# PCB-ARD-MMBOS.net
KiCad netlist of a schematic drawn in EAGLE
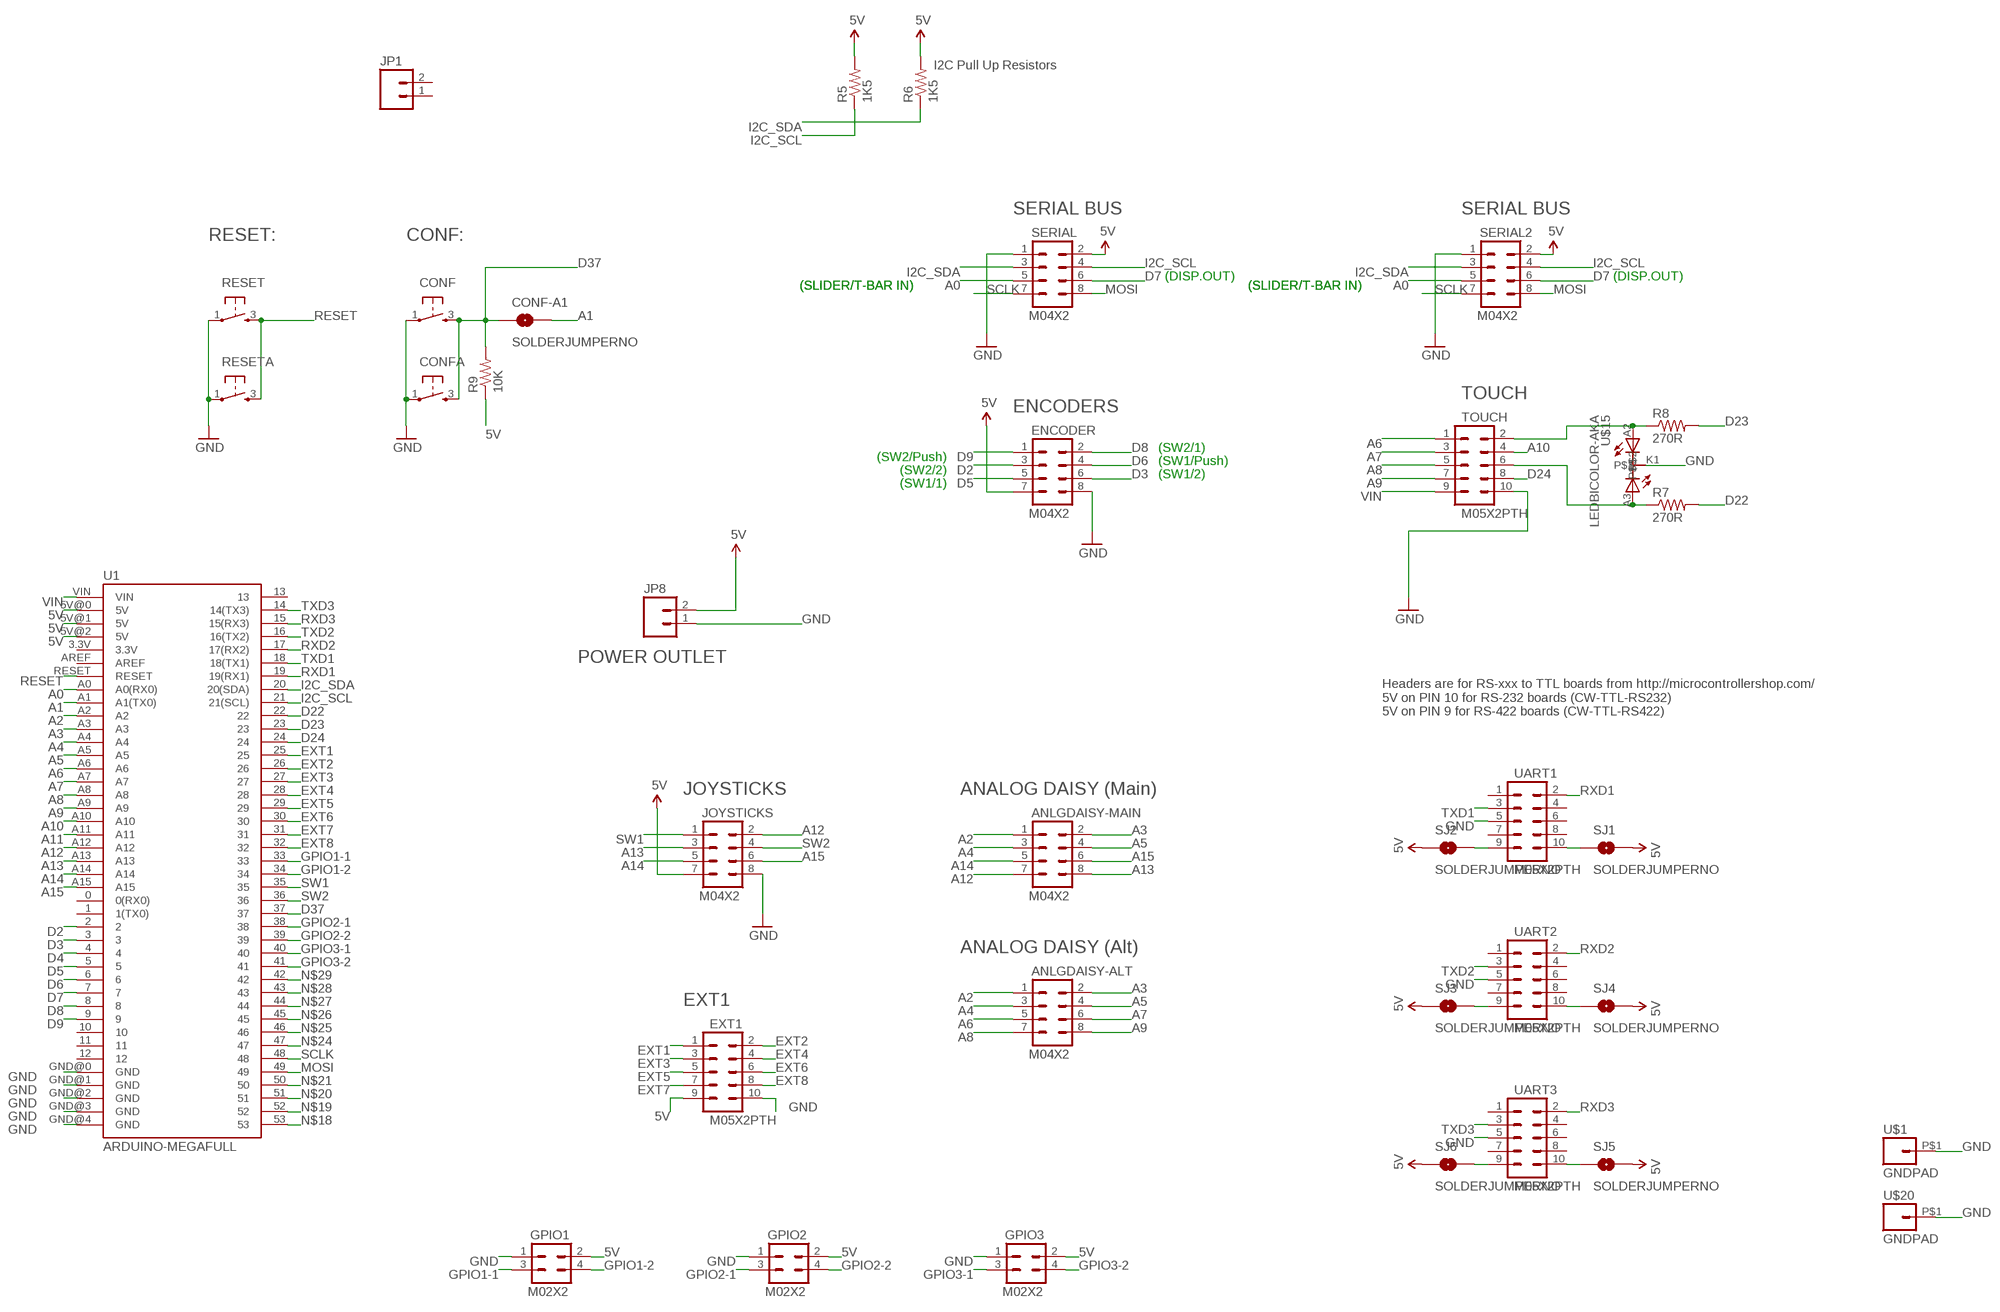
[diagram p0: schematic, sheet 1]

(export (version "E")
  (design (tool "Eeschema 10.0.6"))
  (components
    (comp (ref "ANLGDAISY-ALT")
      (value "M04X2")
      (footprint "eagle-import:2X4")
      (libsource (lib "eagle-import") (part "M04X2"))
    )
    (comp (ref "ANLGDAISY-MAIN")
      (value "M04X2")
      (footprint "eagle-import:2X4")
      (libsource (lib "eagle-import") (part "M04X2"))
    )
    (comp (ref "CONF")
      (value "TAC_SWITCH")
      (footprint "eagle-import:PUSHBUTTON")
      (libsource (lib "eagle-import") (part "TAC_SWITCH"))
    )
    (comp (ref "CONF-A1")
      (value "SOLDERJUMPERNO")
      (footprint "eagle-import:SJ_2S-NO")
      (libsource (lib "eagle-import") (part "SOLDERJUMPERNO"))
    )
    (comp (ref "CONFA")
      (value "TAC_SWITCH")
      (footprint "eagle-import:PUSHBUTTON")
      (libsource (lib "eagle-import") (part "TAC_SWITCH"))
    )
    (comp (ref "ENCODER")
      (value "M04X2")
      (footprint "eagle-import:2X4")
      (libsource (lib "eagle-import") (part "M04X2"))
    )
    (comp (ref "EXT1")
      (value "M05X2PTH")
      (footprint "eagle-import:AVR_ICSP")
      (libsource (lib "eagle-import") (part "M05X2PTH"))
    )
    (comp (ref "GPIO1")
      (value "M02X2")
      (footprint "eagle-import:2X2")
      (libsource (lib "eagle-import") (part "M02X2"))
    )
    (comp (ref "GPIO2")
      (value "M02X2")
      (footprint "eagle-import:2X2")
      (libsource (lib "eagle-import") (part "M02X2"))
    )
    (comp (ref "GPIO3")
      (value "M02X2")
      (footprint "eagle-import:2X2")
      (libsource (lib "eagle-import") (part "M02X2"))
    )
    (comp (ref "JOYSTICKS")
      (value "M04X2")
      (footprint "eagle-import:2X4")
      (libsource (lib "eagle-import") (part "M04X2"))
    )
    (comp (ref "JP1")
      (value "M02PTH")
      (footprint "eagle-import:1X02")
      (libsource (lib "eagle-import") (part "M02PTH"))
    )
    (comp (ref "JP8")
      (value "M02PTH4")
      (footprint "eagle-import:1X02_XTRA_BIG")
      (libsource (lib "eagle-import") (part "M02PTH4"))
    )
    (comp (ref "R5")
      (value "1K5")
      (footprint "eagle-import:0603-RES")
      (libsource (lib "eagle-import") (part "RESISTOR0603-RES"))
    )
    (comp (ref "R6")
      (value "1K5")
      (footprint "eagle-import:0603-RES")
      (libsource (lib "eagle-import") (part "RESISTOR0603-RES"))
    )
    (comp (ref "R7")
      (value "270R")
      (footprint "eagle-import:0603-RES")
      (libsource (lib "eagle-import") (part "RESISTOR0603-RES"))
    )
    (comp (ref "R8")
      (value "270R")
      (footprint "eagle-import:0603-RES")
      (libsource (lib "eagle-import") (part "RESISTOR0603-RES"))
    )
    (comp (ref "R9")
      (value "10K")
      (footprint "eagle-import:0603-RES")
      (libsource (lib "eagle-import") (part "RESISTOR0603-RES"))
    )
    (comp (ref "RESET")
      (value "TAC_SWITCH")
      (footprint "eagle-import:PUSHBUTTON")
      (libsource (lib "eagle-import") (part "TAC_SWITCH"))
    )
    (comp (ref "RESETA")
      (value "TAC_SWITCH")
      (footprint "eagle-import:PUSHBUTTON")
      (libsource (lib "eagle-import") (part "TAC_SWITCH"))
    )
    (comp (ref "SERIAL")
      (value "M04X2")
      (footprint "eagle-import:2X4")
      (libsource (lib "eagle-import") (part "M04X2"))
    )
    (comp (ref "SERIAL2")
      (value "M04X2")
      (footprint "eagle-import:2X4")
      (libsource (lib "eagle-import") (part "M04X2"))
    )
    (comp (ref "SJ1")
      (value "SOLDERJUMPERNO")
      (footprint "eagle-import:SJ_2S-NO")
      (libsource (lib "eagle-import") (part "SOLDERJUMPERNO"))
    )
    (comp (ref "SJ2")
      (value "SOLDERJUMPERNO")
      (footprint "eagle-import:SJ_2S-NO")
      (libsource (lib "eagle-import") (part "SOLDERJUMPERNO"))
    )
    (comp (ref "SJ3")
      (value "SOLDERJUMPERNO")
      (footprint "eagle-import:SJ_2S-NO")
      (libsource (lib "eagle-import") (part "SOLDERJUMPERNO"))
    )
    (comp (ref "SJ4")
      (value "SOLDERJUMPERNO")
      (footprint "eagle-import:SJ_2S-NO")
      (libsource (lib "eagle-import") (part "SOLDERJUMPERNO"))
    )
    (comp (ref "SJ5")
      (value "SOLDERJUMPERNO")
      (footprint "eagle-import:SJ_2S-NO")
      (libsource (lib "eagle-import") (part "SOLDERJUMPERNO"))
    )
    (comp (ref "SJ6")
      (value "SOLDERJUMPERNO")
      (footprint "eagle-import:SJ_2S-NO")
      (libsource (lib "eagle-import") (part "SOLDERJUMPERNO"))
    )
    (comp (ref "TOUCH")
      (value "M05X2PTH")
      (footprint "eagle-import:AVR_ICSP")
      (libsource (lib "eagle-import") (part "M05X2PTH"))
    )
    (comp (ref "U$1")
      (value "GNDPAD")
      (footprint "eagle-import:3.2MMPAD")
      (libsource (lib "eagle-import") (part "GNDPAD"))
    )
    (comp (ref "U$15")
      (value "LEDBICOLOR-AKA")
      (footprint "eagle-import:LED5MM-BICOLOR")
      (libsource (lib "eagle-import") (part "LEDBICOLOR-AKA"))
    )
    (comp (ref "U$20")
      (value "GNDPAD")
      (footprint "eagle-import:3.2MMPAD")
      (libsource (lib "eagle-import") (part "GNDPAD"))
    )
    (comp (ref "U1")
      (value "ARDUINO-MEGAFULL")
      (footprint "eagle-import:ARDUINO_MEGA")
      (libsource (lib "eagle-import") (part "ARDUINO-MEGAFULL"))
    )
    (comp (ref "UART1")
      (value "M05X2PTH")
      (footprint "eagle-import:AVR_ICSP")
      (libsource (lib "eagle-import") (part "M05X2PTH"))
    )
    (comp (ref "UART2")
      (value "M05X2PTH")
      (footprint "eagle-import:AVR_ICSP")
      (libsource (lib "eagle-import") (part "M05X2PTH"))
    )
    (comp (ref "UART3")
      (value "M05X2PTH")
      (footprint "eagle-import:AVR_ICSP")
      (libsource (lib "eagle-import") (part "M05X2PTH"))
    )
  )
  (nets
    (net (code "1") (name "/A0") (class "Default")
      (node (ref "SERIAL") (pin "5") (pinfunction "5_5") (pintype "passive"))
      (node (ref "SERIAL2") (pin "5") (pinfunction "5_5") (pintype "passive"))
      (node (ref "U1") (pin "A0") (pinfunction "A0(RX0)_A0") (pintype "bidirectional"))
    )
    (net (code "2") (name "/A1") (class "Default")
      (node (ref "CONF-A1") (pin "2") (pinfunction "2_2") (pintype "passive"))
      (node (ref "U1") (pin "A1") (pinfunction "A1(TX0)_A1") (pintype "bidirectional"))
    )
    (net (code "3") (name "/A2") (class "Default")
      (node (ref "ANLGDAISY-ALT") (pin "1") (pinfunction "1_1") (pintype "passive"))
      (node (ref "ANLGDAISY-MAIN") (pin "1") (pinfunction "1_1") (pintype "passive"))
      (node (ref "U1") (pin "A2") (pinfunction "A2_A2") (pintype "bidirectional"))
    )
    (net (code "4") (name "/A3") (class "Default")
      (node (ref "ANLGDAISY-ALT") (pin "2") (pinfunction "2_2") (pintype "passive"))
      (node (ref "ANLGDAISY-MAIN") (pin "2") (pinfunction "2_2") (pintype "passive"))
      (node (ref "U1") (pin "A3") (pinfunction "A3_A3") (pintype "bidirectional"))
    )
    (net (code "5") (name "/A4") (class "Default")
      (node (ref "ANLGDAISY-ALT") (pin "3") (pinfunction "3_3") (pintype "passive"))
      (node (ref "ANLGDAISY-MAIN") (pin "3") (pinfunction "3_3") (pintype "passive"))
      (node (ref "U1") (pin "A4") (pinfunction "A4_A4") (pintype "bidirectional"))
    )
    (net (code "6") (name "/A5") (class "Default")
      (node (ref "ANLGDAISY-ALT") (pin "4") (pinfunction "4_4") (pintype "passive"))
      (node (ref "ANLGDAISY-MAIN") (pin "4") (pinfunction "4_4") (pintype "passive"))
      (node (ref "U1") (pin "A5") (pinfunction "A5_A5") (pintype "bidirectional"))
    )
    (net (code "7") (name "/A6") (class "Default")
      (node (ref "ANLGDAISY-ALT") (pin "5") (pinfunction "5_5") (pintype "passive"))
      (node (ref "TOUCH") (pin "1") (pinfunction "1_1") (pintype "passive"))
      (node (ref "U1") (pin "A6") (pinfunction "A6_A6") (pintype "bidirectional"))
    )
    (net (code "8") (name "/A7") (class "Default")
      (node (ref "ANLGDAISY-ALT") (pin "6") (pinfunction "6_6") (pintype "passive"))
      (node (ref "TOUCH") (pin "3") (pinfunction "3_3") (pintype "passive"))
      (node (ref "U1") (pin "A7") (pinfunction "A7_A7") (pintype "bidirectional"))
    )
    (net (code "9") (name "/A8") (class "Default")
      (node (ref "ANLGDAISY-ALT") (pin "7") (pinfunction "7_7") (pintype "passive"))
      (node (ref "TOUCH") (pin "5") (pinfunction "5_5") (pintype "passive"))
      (node (ref "U1") (pin "A8") (pinfunction "A8_A8") (pintype "bidirectional"))
    )
    (net (code "10") (name "/A9") (class "Default")
      (node (ref "ANLGDAISY-ALT") (pin "8") (pinfunction "8_8") (pintype "passive"))
      (node (ref "TOUCH") (pin "7") (pinfunction "7_7") (pintype "passive"))
      (node (ref "U1") (pin "A9") (pinfunction "A9_A9") (pintype "bidirectional"))
    )
    (net (code "11") (name "/A10") (class "Default")
      (node (ref "TOUCH") (pin "4") (pinfunction "4_4") (pintype "passive"))
      (node (ref "U1") (pin "A10") (pinfunction "A10_A10") (pintype "bidirectional"))
    )
    (net (code "12") (name "/A11") (class "Default")
      (node (ref "U1") (pin "A11") (pinfunction "A11_A11") (pintype "bidirectional"))
    )
    (net (code "13") (name "/A12") (class "Default")
      (node (ref "ANLGDAISY-MAIN") (pin "7") (pinfunction "7_7") (pintype "passive"))
      (node (ref "JOYSTICKS") (pin "2") (pinfunction "2_2") (pintype "passive"))
      (node (ref "U1") (pin "A12") (pinfunction "A12_A12") (pintype "bidirectional"))
    )
    (net (code "14") (name "/A13") (class "Default")
      (node (ref "ANLGDAISY-MAIN") (pin "8") (pinfunction "8_8") (pintype "passive"))
      (node (ref "JOYSTICKS") (pin "3") (pinfunction "3_3") (pintype "passive"))
      (node (ref "U1") (pin "A13") (pinfunction "A13_A13") (pintype "bidirectional"))
    )
    (net (code "15") (name "/A14") (class "Default")
      (node (ref "ANLGDAISY-MAIN") (pin "5") (pinfunction "5_5") (pintype "passive"))
      (node (ref "JOYSTICKS") (pin "5") (pinfunction "5_5") (pintype "passive"))
      (node (ref "U1") (pin "A14") (pinfunction "A14_A14") (pintype "bidirectional"))
    )
    (net (code "16") (name "/A15") (class "Default")
      (node (ref "ANLGDAISY-MAIN") (pin "6") (pinfunction "6_6") (pintype "passive"))
      (node (ref "JOYSTICKS") (pin "6") (pinfunction "6_6") (pintype "passive"))
      (node (ref "U1") (pin "A15") (pinfunction "A15_A15") (pintype "bidirectional"))
    )
    (net (code "17") (name "/D2") (class "Default")
      (node (ref "ENCODER") (pin "3") (pinfunction "3_3") (pintype "passive"))
      (node (ref "U1") (pin "2") (pinfunction "2_2") (pintype "bidirectional"))
    )
    (net (code "18") (name "/D3") (class "Default")
      (node (ref "ENCODER") (pin "6") (pinfunction "6_6") (pintype "passive"))
      (node (ref "U1") (pin "3") (pinfunction "3_3") (pintype "bidirectional"))
    )
    (net (code "19") (name "/D4") (class "Default")
      (node (ref "U1") (pin "4") (pinfunction "4_4") (pintype "bidirectional"))
    )
    (net (code "20") (name "/D5") (class "Default")
      (node (ref "ENCODER") (pin "5") (pinfunction "5_5") (pintype "passive"))
      (node (ref "U1") (pin "5") (pinfunction "5_5") (pintype "bidirectional"))
    )
    (net (code "21") (name "/D6") (class "Default")
      (node (ref "ENCODER") (pin "4") (pinfunction "4_4") (pintype "passive"))
      (node (ref "U1") (pin "6") (pinfunction "6_6") (pintype "bidirectional"))
    )
    (net (code "22") (name "/D7") (class "Default")
      (node (ref "SERIAL") (pin "6") (pinfunction "6_6") (pintype "passive"))
      (node (ref "SERIAL2") (pin "6") (pinfunction "6_6") (pintype "passive"))
      (node (ref "U1") (pin "7") (pinfunction "7_7") (pintype "bidirectional"))
    )
    (net (code "23") (name "/D8") (class "Default")
      (node (ref "ENCODER") (pin "2") (pinfunction "2_2") (pintype "passive"))
      (node (ref "U1") (pin "8") (pinfunction "8_8") (pintype "bidirectional"))
    )
    (net (code "24") (name "/D9") (class "Default")
      (node (ref "ENCODER") (pin "1") (pinfunction "1_1") (pintype "passive"))
      (node (ref "U1") (pin "9") (pinfunction "9_9") (pintype "bidirectional"))
    )
    (net (code "25") (name "/D22") (class "Default")
      (node (ref "R7") (pin "2") (pinfunction "2_2") (pintype "passive"))
      (node (ref "U1") (pin "22") (pinfunction "22_22") (pintype "bidirectional"))
    )
    (net (code "26") (name "/D23") (class "Default")
      (node (ref "R8") (pin "2") (pinfunction "2_2") (pintype "passive"))
      (node (ref "U1") (pin "23") (pinfunction "23_23") (pintype "bidirectional"))
    )
    (net (code "27") (name "/D24") (class "Default")
      (node (ref "TOUCH") (pin "8") (pinfunction "8_8") (pintype "passive"))
      (node (ref "U1") (pin "24") (pinfunction "24_24") (pintype "bidirectional"))
    )
    (net (code "28") (name "/D37") (class "Default")
      (node (ref "CONF") (pin "3") (pinfunction "3_3") (pintype "passive"))
      (node (ref "CONF-A1") (pin "1") (pinfunction "1_1") (pintype "passive"))
      (node (ref "CONFA") (pin "3") (pinfunction "3_3") (pintype "passive"))
      (node (ref "R9") (pin "2") (pinfunction "2_2") (pintype "passive"))
      (node (ref "U1") (pin "37") (pinfunction "37_37") (pintype "bidirectional"))
    )
    (net (code "29") (name "/EXT1") (class "Default")
      (node (ref "EXT1") (pin "1") (pinfunction "1_1") (pintype "passive"))
      (node (ref "U1") (pin "25") (pinfunction "25_25") (pintype "bidirectional"))
    )
    (net (code "30") (name "/EXT2") (class "Default")
      (node (ref "EXT1") (pin "2") (pinfunction "2_2") (pintype "passive"))
      (node (ref "U1") (pin "26") (pinfunction "26_26") (pintype "bidirectional"))
    )
    (net (code "31") (name "/EXT3") (class "Default")
      (node (ref "EXT1") (pin "3") (pinfunction "3_3") (pintype "passive"))
      (node (ref "U1") (pin "27") (pinfunction "27_27") (pintype "bidirectional"))
    )
    (net (code "32") (name "/EXT4") (class "Default")
      (node (ref "EXT1") (pin "4") (pinfunction "4_4") (pintype "passive"))
      (node (ref "U1") (pin "28") (pinfunction "28_28") (pintype "bidirectional"))
    )
    (net (code "33") (name "/EXT5") (class "Default")
      (node (ref "EXT1") (pin "5") (pinfunction "5_5") (pintype "passive"))
      (node (ref "U1") (pin "29") (pinfunction "29_29") (pintype "bidirectional"))
    )
    (net (code "34") (name "/EXT6") (class "Default")
      (node (ref "EXT1") (pin "6") (pinfunction "6_6") (pintype "passive"))
      (node (ref "U1") (pin "30") (pinfunction "30_30") (pintype "bidirectional"))
    )
    (net (code "35") (name "/EXT7") (class "Default")
      (node (ref "EXT1") (pin "7") (pinfunction "7_7") (pintype "passive"))
      (node (ref "U1") (pin "31") (pinfunction "31_31") (pintype "bidirectional"))
    )
    (net (code "36") (name "/EXT8") (class "Default")
      (node (ref "EXT1") (pin "8") (pinfunction "8_8") (pintype "passive"))
      (node (ref "U1") (pin "32") (pinfunction "32_32") (pintype "bidirectional"))
    )
    (net (code "37") (name "/GPIO1-1") (class "Default")
      (node (ref "GPIO1") (pin "3") (pinfunction "3_3") (pintype "passive"))
      (node (ref "U1") (pin "33") (pinfunction "33_33") (pintype "bidirectional"))
    )
    (net (code "38") (name "/GPIO1-2") (class "Default")
      (node (ref "GPIO1") (pin "4") (pinfunction "4_4") (pintype "passive"))
      (node (ref "U1") (pin "34") (pinfunction "34_34") (pintype "bidirectional"))
    )
    (net (code "39") (name "/GPIO2-1") (class "Default")
      (node (ref "GPIO2") (pin "3") (pinfunction "3_3") (pintype "passive"))
      (node (ref "U1") (pin "38") (pinfunction "38_38") (pintype "bidirectional"))
    )
    (net (code "40") (name "/GPIO2-2") (class "Default")
      (node (ref "GPIO2") (pin "4") (pinfunction "4_4") (pintype "passive"))
      (node (ref "U1") (pin "39") (pinfunction "39_39") (pintype "bidirectional"))
    )
    (net (code "41") (name "/GPIO3-1") (class "Default")
      (node (ref "GPIO3") (pin "3") (pinfunction "3_3") (pintype "passive"))
      (node (ref "U1") (pin "40") (pinfunction "40_40") (pintype "bidirectional"))
    )
    (net (code "42") (name "/GPIO3-2") (class "Default")
      (node (ref "GPIO3") (pin "4") (pinfunction "4_4") (pintype "passive"))
      (node (ref "U1") (pin "41") (pinfunction "41_41") (pintype "bidirectional"))
    )
    (net (code "43") (name "/I2C_SCL") (class "Default")
      (node (ref "R5") (pin "1") (pinfunction "1_1") (pintype "passive"))
      (node (ref "SERIAL") (pin "4") (pinfunction "4_4") (pintype "passive"))
      (node (ref "SERIAL2") (pin "4") (pinfunction "4_4") (pintype "passive"))
      (node (ref "U1") (pin "21") (pinfunction "21(SCL)_21") (pintype "bidirectional"))
    )
    (net (code "44") (name "/I2C_SDA") (class "Default")
      (node (ref "R6") (pin "1") (pinfunction "1_1") (pintype "passive"))
      (node (ref "SERIAL") (pin "3") (pinfunction "3_3") (pintype "passive"))
      (node (ref "SERIAL2") (pin "3") (pinfunction "3_3") (pintype "passive"))
      (node (ref "U1") (pin "20") (pinfunction "20(SDA)_20") (pintype "bidirectional"))
    )
    (net (code "45") (name "/MOSI") (class "Default")
      (node (ref "SERIAL") (pin "8") (pinfunction "8_8") (pintype "passive"))
      (node (ref "SERIAL2") (pin "8") (pinfunction "8_8") (pintype "passive"))
      (node (ref "U1") (pin "49") (pinfunction "49_49") (pintype "bidirectional"))
    )
    (net (code "46") (name "/N$18") (class "Default")
      (node (ref "U1") (pin "53") (pinfunction "53_53") (pintype "bidirectional"))
    )
    (net (code "47") (name "/N$19") (class "Default")
      (node (ref "U1") (pin "52") (pinfunction "52_52") (pintype "bidirectional"))
    )
    (net (code "48") (name "/N$20") (class "Default")
      (node (ref "U1") (pin "51") (pinfunction "51_51") (pintype "bidirectional"))
    )
    (net (code "49") (name "/N$21") (class "Default")
      (node (ref "U1") (pin "50") (pinfunction "50_50") (pintype "bidirectional"))
    )
    (net (code "50") (name "/N$24") (class "Default")
      (node (ref "U1") (pin "47") (pinfunction "47_47") (pintype "bidirectional"))
    )
    (net (code "51") (name "/N$25") (class "Default")
      (node (ref "U1") (pin "46") (pinfunction "46_46") (pintype "bidirectional"))
    )
    (net (code "52") (name "/N$26") (class "Default")
      (node (ref "U1") (pin "45") (pinfunction "45_45") (pintype "bidirectional"))
    )
    (net (code "53") (name "/N$27") (class "Default")
      (node (ref "U1") (pin "44") (pinfunction "44_44") (pintype "bidirectional"))
    )
    (net (code "54") (name "/N$28") (class "Default")
      (node (ref "U1") (pin "43") (pinfunction "43_43") (pintype "bidirectional"))
    )
    (net (code "55") (name "/N$29") (class "Default")
      (node (ref "U1") (pin "42") (pinfunction "42_42") (pintype "bidirectional"))
    )
    (net (code "56") (name "/RESET") (class "Default")
      (node (ref "RESET") (pin "3") (pinfunction "3_3") (pintype "passive"))
      (node (ref "RESETA") (pin "3") (pinfunction "3_3") (pintype "passive"))
      (node (ref "U1") (pin "RESET") (pinfunction "RESET_RESET") (pintype "bidirectional"))
    )
    (net (code "57") (name "/RXD1") (class "Default")
      (node (ref "U1") (pin "19") (pinfunction "19(RX1)_19") (pintype "bidirectional"))
      (node (ref "UART1") (pin "2") (pinfunction "2_2") (pintype "passive"))
    )
    (net (code "58") (name "/RXD2") (class "Default")
      (node (ref "U1") (pin "17") (pinfunction "17(RX2)_17") (pintype "bidirectional"))
      (node (ref "UART2") (pin "2") (pinfunction "2_2") (pintype "passive"))
    )
    (net (code "59") (name "/RXD3") (class "Default")
      (node (ref "U1") (pin "15") (pinfunction "15(RX3)_15") (pintype "bidirectional"))
      (node (ref "UART3") (pin "2") (pinfunction "2_2") (pintype "passive"))
    )
    (net (code "60") (name "/SCLK") (class "Default")
      (node (ref "SERIAL") (pin "7") (pinfunction "7_7") (pintype "passive"))
      (node (ref "SERIAL2") (pin "7") (pinfunction "7_7") (pintype "passive"))
      (node (ref "U1") (pin "48") (pinfunction "48_48") (pintype "bidirectional"))
    )
    (net (code "61") (name "/SW1") (class "Default")
      (node (ref "JOYSTICKS") (pin "1") (pinfunction "1_1") (pintype "passive"))
      (node (ref "U1") (pin "35") (pinfunction "35_35") (pintype "bidirectional"))
    )
    (net (code "62") (name "/SW2") (class "Default")
      (node (ref "JOYSTICKS") (pin "4") (pinfunction "4_4") (pintype "passive"))
      (node (ref "U1") (pin "36") (pinfunction "36_36") (pintype "bidirectional"))
    )
    (net (code "63") (name "/TXD1") (class "Default")
      (node (ref "U1") (pin "18") (pinfunction "18(TX1)_18") (pintype "bidirectional"))
      (node (ref "UART1") (pin "3") (pinfunction "3_3") (pintype "passive"))
    )
    (net (code "64") (name "/TXD2") (class "Default")
      (node (ref "U1") (pin "16") (pinfunction "16(TX2)_16") (pintype "bidirectional"))
      (node (ref "UART2") (pin "3") (pinfunction "3_3") (pintype "passive"))
    )
    (net (code "65") (name "/TXD3") (class "Default")
      (node (ref "U1") (pin "14") (pinfunction "14(TX3)_14") (pintype "bidirectional"))
      (node (ref "UART3") (pin "3") (pinfunction "3_3") (pintype "passive"))
    )
    (net (code "66") (name "/VIN") (class "Default")
      (node (ref "TOUCH") (pin "9") (pinfunction "9_9") (pintype "passive"))
      (node (ref "U1") (pin "VIN") (pinfunction "VIN_VIN") (pintype "bidirectional"))
    )
    (net (code "67") (name "5V") (class "Default")
      (node (ref "ENCODER") (pin "7") (pinfunction "7_7") (pintype "passive"))
      (node (ref "EXT1") (pin "9") (pinfunction "9_9") (pintype "passive"))
      (node (ref "GPIO1") (pin "2") (pinfunction "2_2") (pintype "passive"))
      (node (ref "GPIO2") (pin "2") (pinfunction "2_2") (pintype "passive"))
      (node (ref "GPIO3") (pin "2") (pinfunction "2_2") (pintype "passive"))
      (node (ref "JOYSTICKS") (pin "7") (pinfunction "7_7") (pintype "passive"))
      (node (ref "JP8") (pin "2") (pinfunction "2_2") (pintype "passive"))
      (node (ref "R5") (pin "2") (pinfunction "2_2") (pintype "passive"))
      (node (ref "R6") (pin "2") (pinfunction "2_2") (pintype "passive"))
      (node (ref "R9") (pin "1") (pinfunction "1_1") (pintype "passive"))
      (node (ref "SERIAL") (pin "2") (pinfunction "2_2") (pintype "passive"))
      (node (ref "SERIAL2") (pin "2") (pinfunction "2_2") (pintype "passive"))
      (node (ref "SJ1") (pin "2") (pinfunction "2_2") (pintype "passive"))
      (node (ref "SJ2") (pin "1") (pinfunction "1_1") (pintype "passive"))
      (node (ref "SJ3") (pin "1") (pinfunction "1_1") (pintype "passive"))
      (node (ref "SJ4") (pin "2") (pinfunction "2_2") (pintype "passive"))
      (node (ref "SJ5") (pin "2") (pinfunction "2_2") (pintype "passive"))
      (node (ref "SJ6") (pin "1") (pinfunction "1_1") (pintype "passive"))
      (node (ref "U1") (pin "5V@0") (pinfunction "5V_5V@0") (pintype "bidirectional"))
      (node (ref "U1") (pin "5V@1") (pinfunction "5V_5V@1") (pintype "bidirectional"))
      (node (ref "U1") (pin "5V@2") (pinfunction "5V_5V@2") (pintype "bidirectional"))
    )
    (net (code "68") (name "GND") (class "Default")
      (node (ref "CONF") (pin "1") (pinfunction "1_1") (pintype "passive"))
      (node (ref "CONFA") (pin "1") (pinfunction "1_1") (pintype "passive"))
      (node (ref "ENCODER") (pin "8") (pinfunction "8_8") (pintype "passive"))
      (node (ref "EXT1") (pin "10") (pinfunction "10_10") (pintype "passive"))
      (node (ref "GPIO1") (pin "1") (pinfunction "1_1") (pintype "passive"))
      (node (ref "GPIO2") (pin "1") (pinfunction "1_1") (pintype "passive"))
      (node (ref "GPIO3") (pin "1") (pinfunction "1_1") (pintype "passive"))
      (node (ref "JOYSTICKS") (pin "8") (pinfunction "8_8") (pintype "passive"))
      (node (ref "JP8") (pin "1") (pinfunction "1_1") (pintype "passive"))
      (node (ref "RESET") (pin "1") (pinfunction "1_1") (pintype "passive"))
      (node (ref "RESETA") (pin "1") (pinfunction "1_1") (pintype "passive"))
      (node (ref "SERIAL") (pin "1") (pinfunction "1_1") (pintype "passive"))
      (node (ref "SERIAL2") (pin "1") (pinfunction "1_1") (pintype "passive"))
      (node (ref "TOUCH") (pin "10") (pinfunction "10_10") (pintype "passive"))
      (node (ref "U$1") (pin "P$1") (pinfunction "1_P$1") (pintype "passive"))
      (node (ref "U$15") (pin "K1") (pinfunction "P$1_K1") (pintype "bidirectional"))
      (node (ref "U$20") (pin "P$1") (pinfunction "1_P$1") (pintype "passive"))
      (node (ref "U1") (pin "GND@0") (pinfunction "GND_GND@0") (pintype "bidirectional"))
      (node (ref "U1") (pin "GND@1") (pinfunction "GND_GND@1") (pintype "bidirectional"))
      (node (ref "U1") (pin "GND@2") (pinfunction "GND_GND@2") (pintype "bidirectional"))
      (node (ref "U1") (pin "GND@3") (pinfunction "GND_GND@3") (pintype "bidirectional"))
      (node (ref "U1") (pin "GND@4") (pinfunction "GND_GND@4") (pintype "bidirectional"))
      (node (ref "UART1") (pin "5") (pinfunction "5_5") (pintype "passive"))
      (node (ref "UART2") (pin "5") (pinfunction "5_5") (pintype "passive"))
      (node (ref "UART3") (pin "5") (pinfunction "5_5") (pintype "passive"))
    )
    (net (code "69") (name "Net-(SJ1-Pad1)") (class "Default")
      (node (ref "SJ1") (pin "1") (pinfunction "1_1") (pintype "passive"))
      (node (ref "UART1") (pin "10") (pinfunction "10_10") (pintype "passive"))
    )
    (net (code "70") (name "Net-(SJ2-Pad2)") (class "Default")
      (node (ref "SJ2") (pin "2") (pinfunction "2_2") (pintype "passive"))
      (node (ref "UART1") (pin "9") (pinfunction "9_9") (pintype "passive"))
    )
    (net (code "71") (name "Net-(SJ3-Pad2)") (class "Default")
      (node (ref "SJ3") (pin "2") (pinfunction "2_2") (pintype "passive"))
      (node (ref "UART2") (pin "9") (pinfunction "9_9") (pintype "passive"))
    )
    (net (code "72") (name "Net-(SJ4-Pad1)") (class "Default")
      (node (ref "SJ4") (pin "1") (pinfunction "1_1") (pintype "passive"))
      (node (ref "UART2") (pin "10") (pinfunction "10_10") (pintype "passive"))
    )
    (net (code "73") (name "Net-(SJ5-Pad1)") (class "Default")
      (node (ref "SJ5") (pin "1") (pinfunction "1_1") (pintype "passive"))
      (node (ref "UART3") (pin "10") (pinfunction "10_10") (pintype "passive"))
    )
    (net (code "74") (name "Net-(SJ6-Pad2)") (class "Default")
      (node (ref "SJ6") (pin "2") (pinfunction "2_2") (pintype "passive"))
      (node (ref "UART3") (pin "9") (pinfunction "9_9") (pintype "passive"))
    )
    (net (code "75") (name "Net-(U$15-P$2)") (class "Default")
      (node (ref "R8") (pin "1") (pinfunction "1_1") (pintype "passive"))
      (node (ref "TOUCH") (pin "2") (pinfunction "2_2") (pintype "passive"))
      (node (ref "U$15") (pin "A2") (pinfunction "P$2_A2") (pintype "bidirectional"))
    )
    (net (code "76") (name "Net-(U$15-P$3)") (class "Default")
      (node (ref "R7") (pin "1") (pinfunction "1_1") (pintype "passive"))
      (node (ref "TOUCH") (pin "6") (pinfunction "6_6") (pintype "passive"))
      (node (ref "U$15") (pin "A3") (pinfunction "P$3_A3") (pintype "bidirectional"))
    )
    (net (code "77") (name "unconnected-(JP1-Pad1)") (class "Default")
      (node (ref "JP1") (pin "1") (pinfunction "1_1") (pintype "passive"))
    )
    (net (code "78") (name "unconnected-(JP1-Pad2)") (class "Default")
      (node (ref "JP1") (pin "2") (pinfunction "2_2") (pintype "passive"))
    )
    (net (code "79") (name "unconnected-(U1-0(RX0)-Pad0)") (class "Default")
      (node (ref "U1") (pin "0") (pinfunction "0(RX0)_0") (pintype "bidirectional"))
    )
    (net (code "80") (name "unconnected-(U1-1(TX0)-Pad1)") (class "Default")
      (node (ref "U1") (pin "1") (pinfunction "1(TX0)_1") (pintype "bidirectional"))
    )
    (net (code "81") (name "unconnected-(U1-Pad3.3V)") (class "Default")
      (node (ref "U1") (pin "3.3V") (pinfunction "3.3V_3.3V") (pintype "bidirectional"))
    )
    (net (code "82") (name "unconnected-(U1-Pad10)") (class "Default")
      (node (ref "U1") (pin "10") (pinfunction "10_10") (pintype "bidirectional"))
    )
    (net (code "83") (name "unconnected-(U1-Pad11)") (class "Default")
      (node (ref "U1") (pin "11") (pinfunction "11_11") (pintype "bidirectional"))
    )
    (net (code "84") (name "unconnected-(U1-Pad12)") (class "Default")
      (node (ref "U1") (pin "12") (pinfunction "12_12") (pintype "bidirectional"))
    )
    (net (code "85") (name "unconnected-(U1-Pad13)") (class "Default")
      (node (ref "U1") (pin "13") (pinfunction "13_13") (pintype "bidirectional"))
    )
    (net (code "86") (name "unconnected-(U1-PadAREF)") (class "Default")
      (node (ref "U1") (pin "AREF") (pinfunction "AREF_AREF") (pintype "bidirectional"))
    )
    (net (code "87") (name "unconnected-(UART1-Pad1)") (class "Default")
      (node (ref "UART1") (pin "1") (pinfunction "1_1") (pintype "passive"))
    )
    (net (code "88") (name "unconnected-(UART1-Pad4)") (class "Default")
      (node (ref "UART1") (pin "4") (pinfunction "4_4") (pintype "passive"))
    )
    (net (code "89") (name "unconnected-(UART1-Pad6)") (class "Default")
      (node (ref "UART1") (pin "6") (pinfunction "6_6") (pintype "passive"))
    )
    (net (code "90") (name "unconnected-(UART1-Pad7)") (class "Default")
      (node (ref "UART1") (pin "7") (pinfunction "7_7") (pintype "passive"))
    )
    (net (code "91") (name "unconnected-(UART1-Pad8)") (class "Default")
      (node (ref "UART1") (pin "8") (pinfunction "8_8") (pintype "passive"))
    )
    (net (code "92") (name "unconnected-(UART2-Pad1)") (class "Default")
      (node (ref "UART2") (pin "1") (pinfunction "1_1") (pintype "passive"))
    )
    (net (code "93") (name "unconnected-(UART2-Pad4)") (class "Default")
      (node (ref "UART2") (pin "4") (pinfunction "4_4") (pintype "passive"))
    )
    (net (code "94") (name "unconnected-(UART2-Pad6)") (class "Default")
      (node (ref "UART2") (pin "6") (pinfunction "6_6") (pintype "passive"))
    )
    (net (code "95") (name "unconnected-(UART2-Pad7)") (class "Default")
      (node (ref "UART2") (pin "7") (pinfunction "7_7") (pintype "passive"))
    )
    (net (code "96") (name "unconnected-(UART2-Pad8)") (class "Default")
      (node (ref "UART2") (pin "8") (pinfunction "8_8") (pintype "passive"))
    )
    (net (code "97") (name "unconnected-(UART3-Pad1)") (class "Default")
      (node (ref "UART3") (pin "1") (pinfunction "1_1") (pintype "passive"))
    )
    (net (code "98") (name "unconnected-(UART3-Pad4)") (class "Default")
      (node (ref "UART3") (pin "4") (pinfunction "4_4") (pintype "passive"))
    )
    (net (code "99") (name "unconnected-(UART3-Pad6)") (class "Default")
      (node (ref "UART3") (pin "6") (pinfunction "6_6") (pintype "passive"))
    )
    (net (code "100") (name "unconnected-(UART3-Pad7)") (class "Default")
      (node (ref "UART3") (pin "7") (pinfunction "7_7") (pintype "passive"))
    )
    (net (code "101") (name "unconnected-(UART3-Pad8)") (class "Default")
      (node (ref "UART3") (pin "8") (pinfunction "8_8") (pintype "passive"))
    )
  )
)
